# devkit.net
KiCad netlist of a schematic drawn in EAGLE
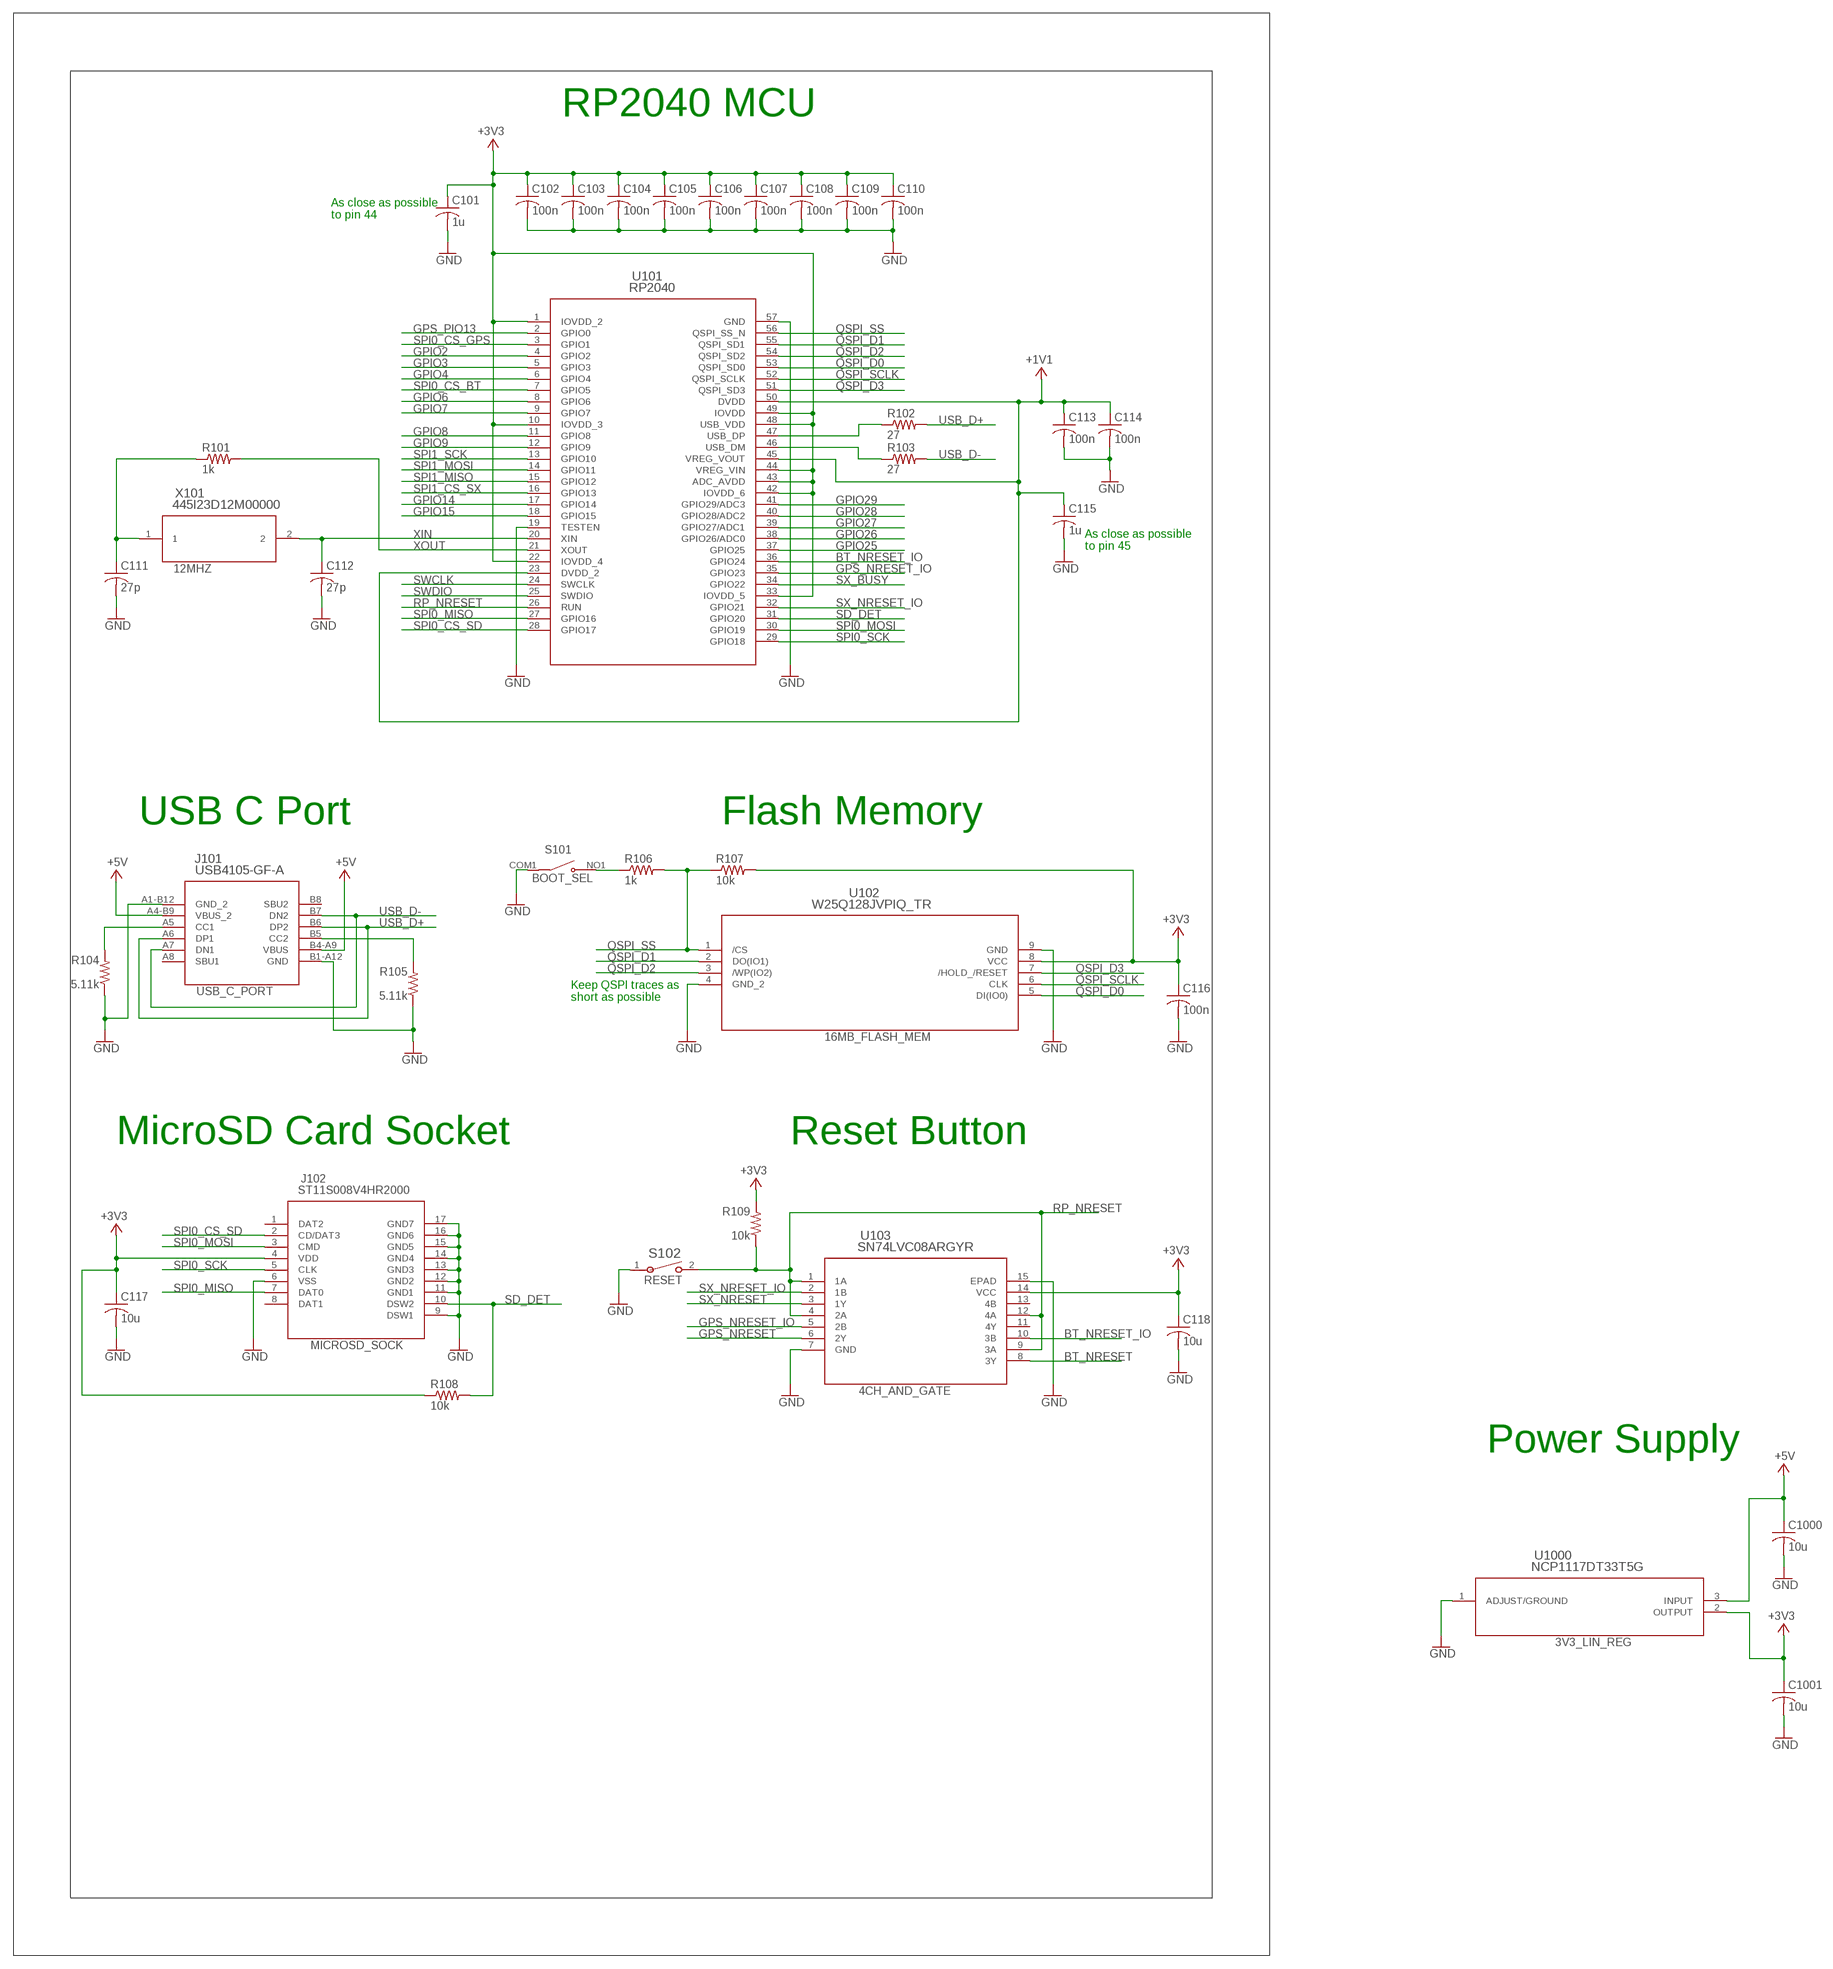
[diagram p0: schematic, sheet 1]
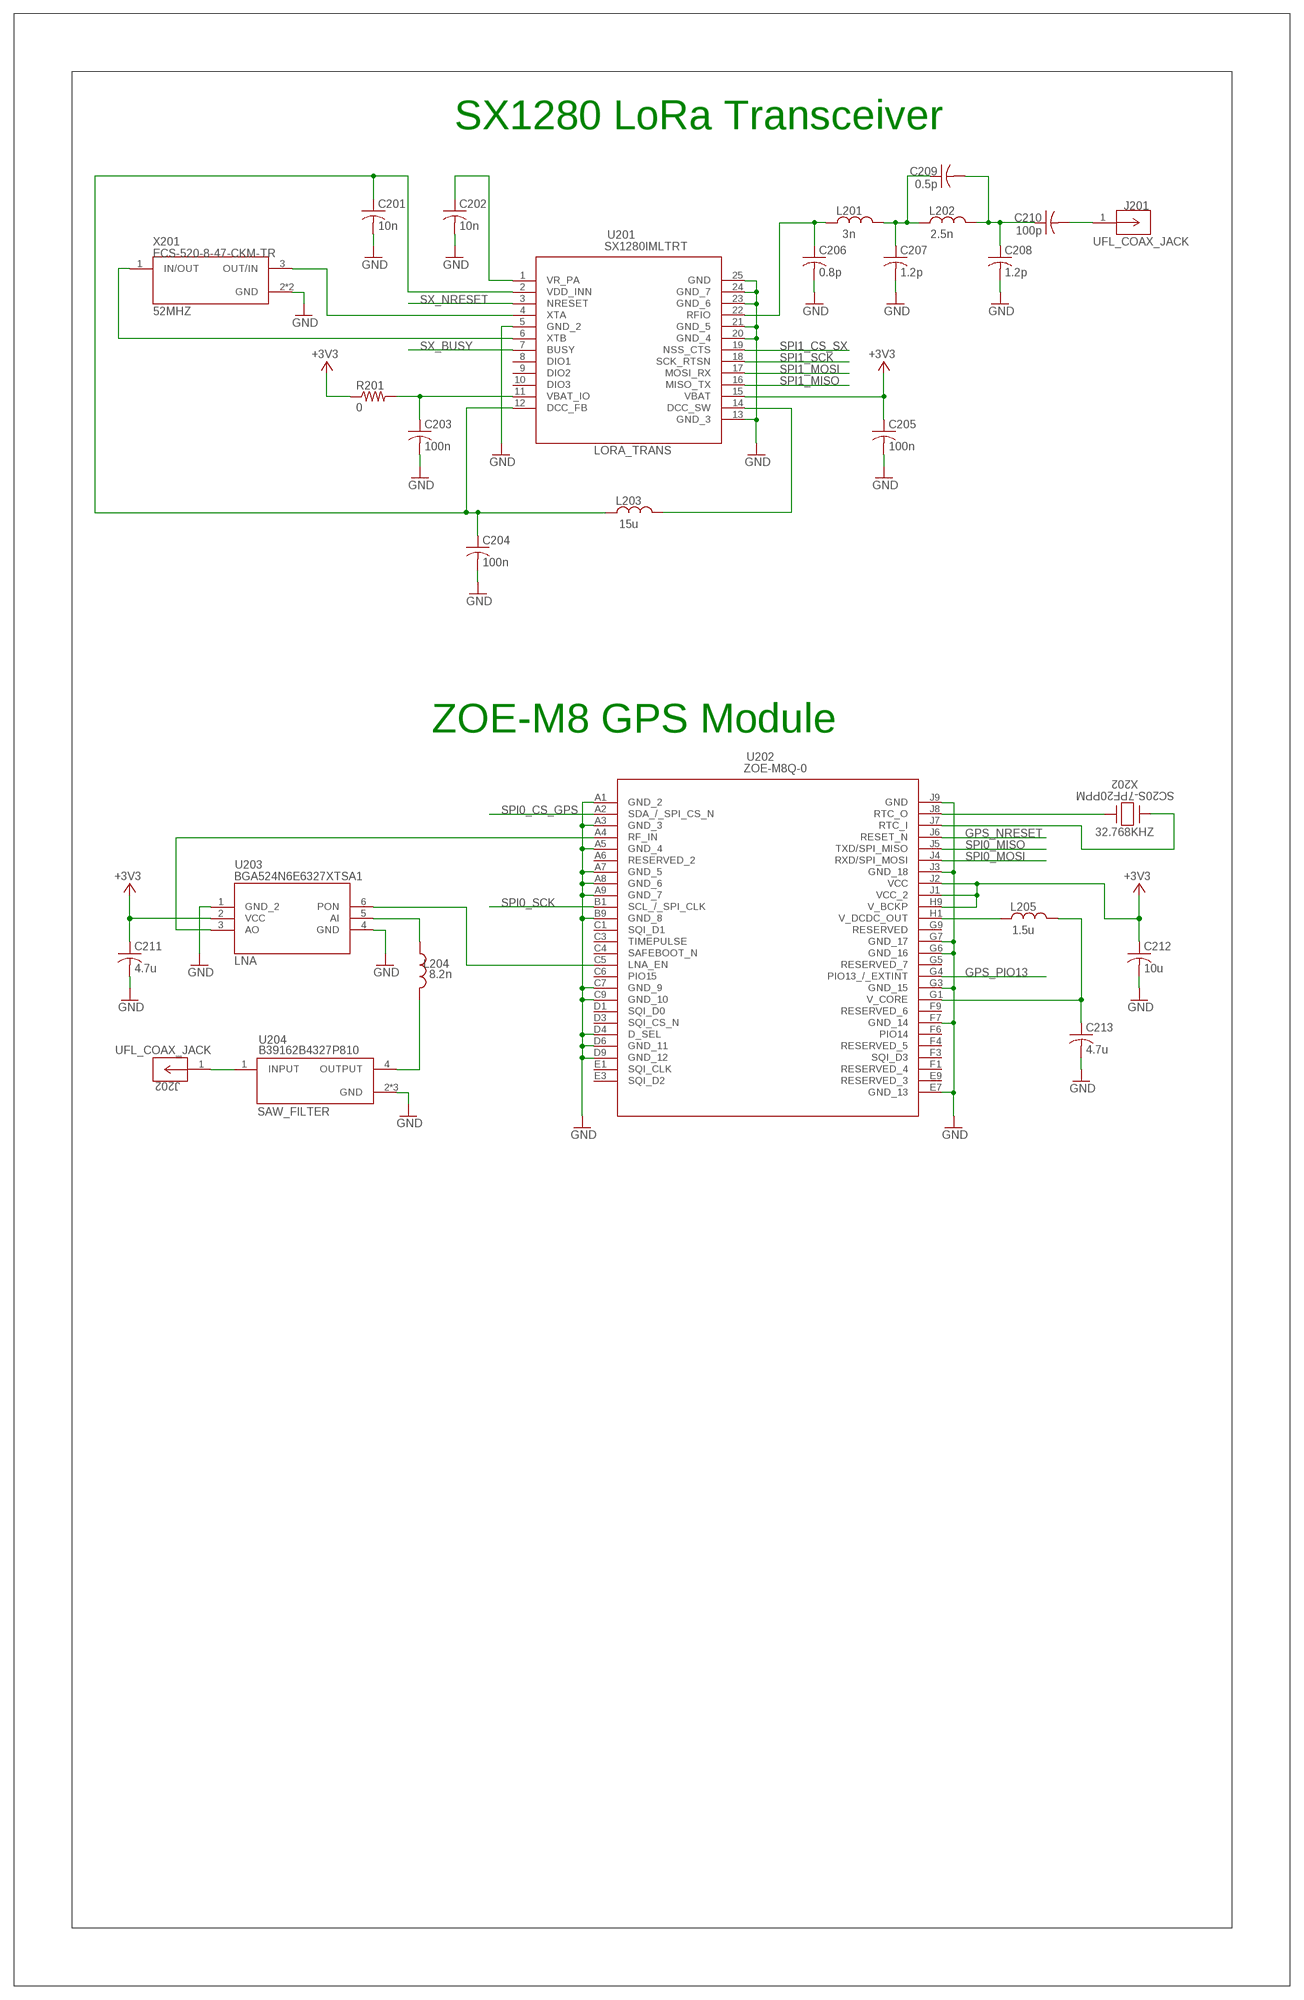
[diagram p1: schematic, sheet 2]

(export (version "E")
  (design (tool "Eeschema 10.0.6"))
  (components
    (comp (ref "C101")
      (value "1u")
      (footprint "eagle-import:C0402")
      (libsource (lib "eagle-import") (part "C-USC0402"))
    )
    (comp (ref "C102")
      (value "100n")
      (footprint "eagle-import:C0402")
      (libsource (lib "eagle-import") (part "C-USC0402"))
    )
    (comp (ref "C103")
      (value "100n")
      (footprint "eagle-import:C0402")
      (libsource (lib "eagle-import") (part "C-USC0402"))
    )
    (comp (ref "C104")
      (value "100n")
      (footprint "eagle-import:C0402")
      (libsource (lib "eagle-import") (part "C-USC0402"))
    )
    (comp (ref "C105")
      (value "100n")
      (footprint "eagle-import:C0402")
      (libsource (lib "eagle-import") (part "C-USC0402"))
    )
    (comp (ref "C106")
      (value "100n")
      (footprint "eagle-import:C0402")
      (libsource (lib "eagle-import") (part "C-USC0402"))
    )
    (comp (ref "C107")
      (value "100n")
      (footprint "eagle-import:C0402")
      (libsource (lib "eagle-import") (part "C-USC0402"))
    )
    (comp (ref "C108")
      (value "100n")
      (footprint "eagle-import:C0402")
      (libsource (lib "eagle-import") (part "C-USC0402"))
    )
    (comp (ref "C109")
      (value "100n")
      (footprint "eagle-import:C0402")
      (libsource (lib "eagle-import") (part "C-USC0402"))
    )
    (comp (ref "C110")
      (value "100n")
      (footprint "eagle-import:C0402")
      (libsource (lib "eagle-import") (part "C-USC0402"))
    )
    (comp (ref "C111")
      (value "27p")
      (footprint "eagle-import:C0402")
      (libsource (lib "eagle-import") (part "C-USC0402"))
    )
    (comp (ref "C112")
      (value "27p")
      (footprint "eagle-import:C0402")
      (libsource (lib "eagle-import") (part "C-USC0402"))
    )
    (comp (ref "C113")
      (value "100n")
      (footprint "eagle-import:C0402")
      (libsource (lib "eagle-import") (part "C-USC0402"))
    )
    (comp (ref "C114")
      (value "100n")
      (footprint "eagle-import:C0402")
      (libsource (lib "eagle-import") (part "C-USC0402"))
    )
    (comp (ref "C115")
      (value "1u")
      (footprint "eagle-import:C0402")
      (libsource (lib "eagle-import") (part "C-USC0402"))
    )
    (comp (ref "C116")
      (value "100n")
      (footprint "eagle-import:C0402")
      (libsource (lib "eagle-import") (part "C-USC0402"))
    )
    (comp (ref "C117")
      (value "10u")
      (footprint "eagle-import:C0402")
      (libsource (lib "eagle-import") (part "C-USC0402"))
    )
    (comp (ref "C118")
      (value "10u")
      (footprint "eagle-import:C0402")
      (libsource (lib "eagle-import") (part "C-USC0402"))
    )
    (comp (ref "C1000")
      (value "10u")
      (footprint "eagle-import:C0402")
      (libsource (lib "eagle-import") (part "C-USC0402"))
    )
    (comp (ref "C1001")
      (value "10u")
      (footprint "eagle-import:C0402")
      (libsource (lib "eagle-import") (part "C-USC0402"))
    )
    (comp (ref "J101")
      (value "USB4105-GF-A")
      (footprint "eagle-import:USB4105_GCT")
      (description "USB_C_PORT")
      (fields (field (name "COPYRIGHT") "Copyright (C) 2022 Ultra Librarian. All rights reserved."))
      (libsource (lib "eagle-import") (part "USB4105-GF-A"))
    )
    (comp (ref "J102")
      (value "ST11S008V4HR2000")
      (footprint "eagle-import:ST11S008V4HR2000_JAE")
      (description "MICROSD_SOCK")
      (fields (field (name "COPYRIGHT") "Copyright (C) 2022 Ultra Librarian. All rights reserved."))
      (libsource (lib "eagle-import") (part "ST11S008V4HR2000"))
    )
    (comp (ref "R101")
      (value "1k")
      (footprint "eagle-import:R0402")
      (libsource (lib "eagle-import") (part "R-US_R0402"))
    )
    (comp (ref "R102")
      (value "27")
      (footprint "eagle-import:R0402")
      (libsource (lib "eagle-import") (part "R-US_R0402"))
    )
    (comp (ref "R103")
      (value "27")
      (footprint "eagle-import:R0402")
      (libsource (lib "eagle-import") (part "R-US_R0402"))
    )
    (comp (ref "R104")
      (value "5.11k")
      (footprint "eagle-import:R0402")
      (libsource (lib "eagle-import") (part "R-US_R0402"))
    )
    (comp (ref "R105")
      (value "5.11k")
      (footprint "eagle-import:R0402")
      (libsource (lib "eagle-import") (part "R-US_R0402"))
    )
    (comp (ref "R106")
      (value "1k")
      (footprint "eagle-import:R0402")
      (libsource (lib "eagle-import") (part "R-US_R0402"))
    )
    (comp (ref "R107")
      (value "10k")
      (footprint "eagle-import:R0402")
      (libsource (lib "eagle-import") (part "R-US_R0402"))
    )
    (comp (ref "R108")
      (value "10k")
      (footprint "eagle-import:R0402")
      (libsource (lib "eagle-import") (part "R-US_R0402"))
    )
    (comp (ref "R109")
      (value "10k")
      (footprint "eagle-import:R0402")
      (libsource (lib "eagle-import") (part "R-US_R0402"))
    )
    (comp (ref "S101")
      (value "SDA01H1SBD")
      (footprint "eagle-import:SW_SDA01H1SBD")
      (description "BOOT_SEL")
      (fields (field (name "DIGI-KEY_PART_NUMBER") "CKN10358-ND") (field (name "MF") "C&K"))
      (libsource (lib "eagle-import") (part "SDA01H1SBD"))
    )
    (comp (ref "S102")
      (value "PTS820J25MSMTRLFS")
      (footprint "eagle-import:SW2_PTS820J25MSMTRLFS_CNK")
      (description "RESET")
      (fields (field (name "COPYRIGHT") "Copyright (C) 2022 Ultra Librarian. All rights reserved."))
      (libsource (lib "eagle-import") (part "PTS820J25MSMTRLFS"))
    )
    (comp (ref "U101")
      (value "RP2040")
      (footprint "eagle-import:IC57_RP2040")
      (fields
        (field (name "MANUFACTURER_PART_NUMBER") "SC0908(13)")
        (field (name "COPYRIGHT") "Copyright (C) 2022 Ultra Librarian. All rights reserved.")
      )
      (libsource (lib "eagle-import") (part "SC0908(13)"))
    )
    (comp (ref "U102")
      (value "W25Q128JVPIQ_TR")
      (footprint "eagle-import:WSON-8_6X5_WIN")
      (description "16MB_FLASH_MEM")
      (fields
        (field (name "MANUFACTURER_PART_NUMBER") "W25Q128JVPIQ TR")
        (field (name "COPYRIGHT") "Copyright (C) 2022 Ultra Librarian. All rights reserved.")
      )
      (libsource (lib "eagle-import") (part "W25Q128JVPIQ_TR"))
    )
    (comp (ref "U103")
      (value "SN74LVC08ARGYR")
      (footprint "eagle-import:RGY14_2P05X2P05")
      (description "4CH_AND_GATE")
      (fields (field (name "COPYRIGHT") "Copyright (C) 2022 Ultra Librarian. All rights reserved."))
      (libsource (lib "eagle-import") (part "SN74LVC08ARGYR"))
    )
    (comp (ref "U1000")
      (value "NCP1117DT33T5G")
      (footprint "eagle-import:DPAK-3_ONS")
      (description "3V3_LIN_REG")
      (fields (field (name "COPYRIGHT") "Copyright (C) 2022 Ultra Librarian. All rights reserved."))
      (libsource (lib "eagle-import") (part "NCP1117DT33T5G"))
    )
    (comp (ref "X101")
      (value "445I23D12M00000")
      (footprint "eagle-import:445I23D12M00000_CTS")
      (description "12MHZ")
      (fields (field (name "COPYRIGHT") "Copyright (C) 2022 Ultra Librarian. All rights reserved."))
      (libsource (lib "eagle-import") (part "445I23D12M00000"))
    )
    (comp (ref "C201")
      (value "10n")
      (footprint "eagle-import:C0402")
      (libsource (lib "eagle-import") (part "C-USC0402"))
    )
    (comp (ref "C202")
      (value "10n")
      (footprint "eagle-import:C0402")
      (libsource (lib "eagle-import") (part "C-USC0402"))
    )
    (comp (ref "C203")
      (value "100n")
      (footprint "eagle-import:C0402")
      (libsource (lib "eagle-import") (part "C-USC0402"))
    )
    (comp (ref "C204")
      (value "100n")
      (footprint "eagle-import:C0402")
      (libsource (lib "eagle-import") (part "C-USC0402"))
    )
    (comp (ref "C205")
      (value "100n")
      (footprint "eagle-import:C0402")
      (libsource (lib "eagle-import") (part "C-USC0402"))
    )
    (comp (ref "C206")
      (value "0.8p")
      (footprint "eagle-import:C0402")
      (libsource (lib "eagle-import") (part "C-USC0402"))
    )
    (comp (ref "C207")
      (value "1.2p")
      (footprint "eagle-import:C0402")
      (libsource (lib "eagle-import") (part "C-USC0402"))
    )
    (comp (ref "C208")
      (value "1.2p")
      (footprint "eagle-import:C0402")
      (libsource (lib "eagle-import") (part "C-USC0402"))
    )
    (comp (ref "C209")
      (value "0.5p")
      (footprint "eagle-import:C0402")
      (libsource (lib "eagle-import") (part "C-USC0402"))
    )
    (comp (ref "C210")
      (value "100p")
      (footprint "eagle-import:C0402")
      (libsource (lib "eagle-import") (part "C-USC0402"))
    )
    (comp (ref "C211")
      (value "4.7u")
      (footprint "eagle-import:C0402")
      (libsource (lib "eagle-import") (part "C-USC0402"))
    )
    (comp (ref "C212")
      (value "10u")
      (footprint "eagle-import:C0402")
      (libsource (lib "eagle-import") (part "C-USC0402"))
    )
    (comp (ref "C213")
      (value "4.7u")
      (footprint "eagle-import:C0402")
      (libsource (lib "eagle-import") (part "C-USC0402"))
    )
    (comp (ref "J201")
      (value "CONUFL001-SMD-T")
      (footprint "eagle-import:CONN_CONUFL001-SMD-T_LNX")
      (description "UFL_COAX_JACK")
      (fields (field (name "COPYRIGHT") "Copyright (C) 2022 Ultra Librarian. All rights reserved."))
      (libsource (lib "eagle-import") (part "CONUFL001-SMD-T"))
    )
    (comp (ref "J202")
      (value "CONUFL001-SMD-T")
      (footprint "eagle-import:CONN_CONUFL001-SMD-T_LNX")
      (description "UFL_COAX_JACK")
      (fields (field (name "COPYRIGHT") "Copyright (C) 2022 Ultra Librarian. All rights reserved."))
      (libsource (lib "eagle-import") (part "CONUFL001-SMD-T"))
    )
    (comp (ref "L201")
      (value "3n")
      (footprint "eagle-import:INDC1006X60N")
      (libsource (lib "eagle-import") (part "LCHIP-0402(1006-METRIC)_"))
    )
    (comp (ref "L202")
      (value "2.5n")
      (footprint "eagle-import:INDC1006X60N")
      (libsource (lib "eagle-import") (part "LCHIP-0402(1006-METRIC)_"))
    )
    (comp (ref "L203")
      (value "15u")
      (footprint "eagle-import:INDC2009X120")
      (libsource (lib "eagle-import") (part "LCHIP-0805(2012-METRIC)_"))
    )
    (comp (ref "L204")
      (value "8.2n")
      (footprint "eagle-import:INDC1006X60N")
      (libsource (lib "eagle-import") (part "LCHIP-0402(1006-METRIC)_"))
    )
    (comp (ref "L205")
      (value "1.5u")
      (footprint "eagle-import:INDC2009X120")
      (libsource (lib "eagle-import") (part "LCHIP-0805(2012-METRIC)_"))
    )
    (comp (ref "R201")
      (value "0")
      (footprint "eagle-import:R0402")
      (libsource (lib "eagle-import") (part "R-US_R0402"))
    )
    (comp (ref "U201")
      (value "SX1280IMLTRT")
      (footprint "eagle-import:QFN24_4X4_SEM")
      (description "LORA_TRANS")
      (fields (field (name "COPYRIGHT") "Copyright (C) 2022 Ultra Librarian. All rights reserved."))
      (libsource (lib "eagle-import") (part "SX1280IMLTRT"))
    )
    (comp (ref "U202")
      (value "ZOE-M8Q-0")
      (footprint "eagle-import:BGA_E-M8Q-0_UBL")
      (fields (field (name "COPYRIGHT") "Copyright (C) 2022 Ultra Librarian. All rights reserved."))
      (libsource (lib "eagle-import") (part "ZOE-M8Q-0"))
    )
    (comp (ref "U203")
      (value "BGA524N6E6327XTSA1")
      (footprint "eagle-import:PG-TSNP-6-2_INF")
      (description "LNA")
      (fields (field (name "COPYRIGHT") "Copyright (C) 2022 Ultra Librarian. All rights reserved."))
      (libsource (lib "eagle-import") (part "BGA524N6E6327XTSA1"))
    )
    (comp (ref "U204")
      (value "B39162B4327P810")
      (footprint "eagle-import:FIL_B39162B4327P810")
      (fields
        (field (name "DIGI-KEY_PART_NUMBER") "495-7424-2-ND")
        (field (name "MF") "Qualcomm (RF360")
        (field (name "DECRIPTION") "SAW_FILTER")
      )
      (libsource (lib "eagle-import") (part "B39162B4327P810"))
    )
    (comp (ref "X201")
      (value "ECS-520-8-47-CKM-TR")
      (footprint "eagle-import:XTAL_ECS-520-8-47-CKM-TR")
      (description "52MHZ")
      (fields (field (name "DIGI-KEY_PART_NUMBER") "XC2554TR-ND") (field (name "MF") "ECS Inc."))
      (libsource (lib "eagle-import") (part "ECS-520-8-47-CKM-TR"))
    )
    (comp (ref "X202")
      (value "SC20S-7PF20PPM")
      (footprint "eagle-import:XTAL_SC-20S_EPS")
      (description "32.768KHZ")
      (fields (field (name "COPYRIGHT") "Copyright (C) 2022 Ultra Librarian. All rights reserved."))
      (libsource (lib "eagle-import") (part "SC20S-7PF20PPM"))
    )
  )
  (nets
    (net (code "1") (name "+1V1") (class "Default")
      (node (ref "C113") (pin "1") (pinfunction "1_1") (pintype "passive"))
      (node (ref "C114") (pin "1") (pinfunction "1_1") (pintype "passive"))
      (node (ref "C115") (pin "1") (pinfunction "1_1") (pintype "passive"))
      (node (ref "U101") (pin "23") (pinfunction "DVDD_2_23") (pintype "power_in"))
      (node (ref "U101") (pin "45") (pinfunction "VREG_VOUT_45") (pintype "output"))
      (node (ref "U101") (pin "50") (pinfunction "DVDD_50") (pintype "power_in"))
    )
    (net (code "2") (name "+3V3") (class "Default")
      (node (ref "C1001") (pin "1") (pinfunction "1_1") (pintype "passive"))
      (node (ref "C101") (pin "1") (pinfunction "1_1") (pintype "passive"))
      (node (ref "C102") (pin "1") (pinfunction "1_1") (pintype "passive"))
      (node (ref "C103") (pin "1") (pinfunction "1_1") (pintype "passive"))
      (node (ref "C104") (pin "1") (pinfunction "1_1") (pintype "passive"))
      (node (ref "C105") (pin "1") (pinfunction "1_1") (pintype "passive"))
      (node (ref "C106") (pin "1") (pinfunction "1_1") (pintype "passive"))
      (node (ref "C107") (pin "1") (pinfunction "1_1") (pintype "passive"))
      (node (ref "C108") (pin "1") (pinfunction "1_1") (pintype "passive"))
      (node (ref "C109") (pin "1") (pinfunction "1_1") (pintype "passive"))
      (node (ref "C110") (pin "1") (pinfunction "1_1") (pintype "passive"))
      (node (ref "C116") (pin "1") (pinfunction "1_1") (pintype "passive"))
      (node (ref "C117") (pin "1") (pinfunction "1_1") (pintype "passive"))
      (node (ref "C118") (pin "1") (pinfunction "1_1") (pintype "passive"))
      (node (ref "C205") (pin "1") (pinfunction "1_1") (pintype "passive"))
      (node (ref "C211") (pin "1") (pinfunction "1_1") (pintype "passive"))
      (node (ref "C212") (pin "1") (pinfunction "1_1") (pintype "passive"))
      (node (ref "J102") (pin "4") (pinfunction "VDD_4") (pintype "power_in"))
      (node (ref "R107") (pin "2") (pinfunction "2_2") (pintype "passive"))
      (node (ref "R108") (pin "1") (pinfunction "1_1") (pintype "passive"))
      (node (ref "R109") (pin "2") (pinfunction "2_2") (pintype "passive"))
      (node (ref "R201") (pin "1") (pinfunction "1_1") (pintype "passive"))
      (node (ref "U1000") (pin "2") (pinfunction "OUTPUT_2") (pintype "output"))
      (node (ref "U101") (pin "1") (pinfunction "IOVDD_2_1") (pintype "power_in"))
      (node (ref "U101") (pin "10") (pinfunction "IOVDD_3_10") (pintype "power_in"))
      (node (ref "U101") (pin "22") (pinfunction "IOVDD_4_22") (pintype "power_in"))
      (node (ref "U101") (pin "33") (pinfunction "IOVDD_5_33") (pintype "power_in"))
      (node (ref "U101") (pin "42") (pinfunction "IOVDD_6_42") (pintype "power_in"))
      (node (ref "U101") (pin "43") (pinfunction "ADC_AVDD_43") (pintype "power_in"))
      (node (ref "U101") (pin "44") (pinfunction "VREG_VIN_44") (pintype "passive"))
      (node (ref "U101") (pin "48") (pinfunction "USB_VDD_48") (pintype "power_in"))
      (node (ref "U101") (pin "49") (pinfunction "IOVDD_49") (pintype "power_in"))
      (node (ref "U102") (pin "8") (pinfunction "VCC_8") (pintype "power_in"))
      (node (ref "U103") (pin "14") (pinfunction "VCC_14") (pintype "power_in"))
      (node (ref "U201") (pin "15") (pinfunction "VBAT_15") (pintype "power_in"))
      (node (ref "U202") (pin "H9") (pinfunction "V_BCKP_H9") (pintype "passive"))
      (node (ref "U202") (pin "J1") (pinfunction "VCC_2_J1") (pintype "power_in"))
      (node (ref "U202") (pin "J2") (pinfunction "VCC_J2") (pintype "power_in"))
      (node (ref "U203") (pin "2") (pinfunction "VCC_2") (pintype "power_in"))
    )
    (net (code "3") (name "+5V") (class "Default")
      (node (ref "C1000") (pin "1") (pinfunction "1_1") (pintype "passive"))
      (node (ref "J101") (pin "A4-B9") (pinfunction "VBUS_2_A4-B9") (pintype "power_in"))
      (node (ref "J101") (pin "B4-A9") (pinfunction "VBUS_B4-A9") (pintype "power_in"))
      (node (ref "U1000") (pin "3") (pinfunction "INPUT_3") (pintype "input"))
    )
    (net (code "4") (name "BT_NRESET") (class "Default")
      (node (ref "U103") (pin "8") (pinfunction "3Y_8") (pintype "output"))
    )
    (net (code "5") (name "BT_NRESET_IO") (class "Default")
      (node (ref "U101") (pin "36") (pinfunction "GPIO24_36") (pintype "bidirectional"))
      (node (ref "U103") (pin "10") (pinfunction "3B_10") (pintype "input"))
    )
    (net (code "6") (name "GND") (class "Default")
      (node (ref "C1000") (pin "2") (pinfunction "2_2") (pintype "passive"))
      (node (ref "C1001") (pin "2") (pinfunction "2_2") (pintype "passive"))
      (node (ref "C101") (pin "2") (pinfunction "2_2") (pintype "passive"))
      (node (ref "C102") (pin "2") (pinfunction "2_2") (pintype "passive"))
      (node (ref "C103") (pin "2") (pinfunction "2_2") (pintype "passive"))
      (node (ref "C104") (pin "2") (pinfunction "2_2") (pintype "passive"))
      (node (ref "C105") (pin "2") (pinfunction "2_2") (pintype "passive"))
      (node (ref "C106") (pin "2") (pinfunction "2_2") (pintype "passive"))
      (node (ref "C107") (pin "2") (pinfunction "2_2") (pintype "passive"))
      (node (ref "C108") (pin "2") (pinfunction "2_2") (pintype "passive"))
      (node (ref "C109") (pin "2") (pinfunction "2_2") (pintype "passive"))
      (node (ref "C110") (pin "2") (pinfunction "2_2") (pintype "passive"))
      (node (ref "C111") (pin "2") (pinfunction "2_2") (pintype "passive"))
      (node (ref "C112") (pin "2") (pinfunction "2_2") (pintype "passive"))
      (node (ref "C113") (pin "2") (pinfunction "2_2") (pintype "passive"))
      (node (ref "C114") (pin "2") (pinfunction "2_2") (pintype "passive"))
      (node (ref "C115") (pin "2") (pinfunction "2_2") (pintype "passive"))
      (node (ref "C116") (pin "2") (pinfunction "2_2") (pintype "passive"))
      (node (ref "C117") (pin "2") (pinfunction "2_2") (pintype "passive"))
      (node (ref "C118") (pin "2") (pinfunction "2_2") (pintype "passive"))
      (node (ref "C201") (pin "2") (pinfunction "2_2") (pintype "passive"))
      (node (ref "C202") (pin "2") (pinfunction "2_2") (pintype "passive"))
      (node (ref "C203") (pin "2") (pinfunction "2_2") (pintype "passive"))
      (node (ref "C204") (pin "2") (pinfunction "2_2") (pintype "passive"))
      (node (ref "C205") (pin "2") (pinfunction "2_2") (pintype "passive"))
      (node (ref "C206") (pin "2") (pinfunction "2_2") (pintype "passive"))
      (node (ref "C207") (pin "2") (pinfunction "2_2") (pintype "passive"))
      (node (ref "C208") (pin "2") (pinfunction "2_2") (pintype "passive"))
      (node (ref "C211") (pin "2") (pinfunction "2_2") (pintype "passive"))
      (node (ref "C212") (pin "2") (pinfunction "2_2") (pintype "passive"))
      (node (ref "C213") (pin "2") (pinfunction "2_2") (pintype "passive"))
      (node (ref "J101") (pin "A1-B12") (pinfunction "GND_2_A1-B12") (pintype "passive"))
      (node (ref "J101") (pin "B1-A12") (pinfunction "GND_B1-A12") (pintype "passive"))
      (node (ref "J102") (pin "11") (pinfunction "GND1_11") (pintype "passive"))
      (node (ref "J102") (pin "12") (pinfunction "GND2_12") (pintype "passive"))
      (node (ref "J102") (pin "13") (pinfunction "GND3_13") (pintype "passive"))
      (node (ref "J102") (pin "14") (pinfunction "GND4_14") (pintype "passive"))
      (node (ref "J102") (pin "15") (pinfunction "GND5_15") (pintype "passive"))
      (node (ref "J102") (pin "16") (pinfunction "GND6_16") (pintype "passive"))
      (node (ref "J102") (pin "17") (pinfunction "GND7_17") (pintype "passive"))
      (node (ref "J102") (pin "6") (pinfunction "VSS_6") (pintype "passive"))
      (node (ref "J102") (pin "9") (pinfunction "DSW1_9") (pintype "bidirectional"))
      (node (ref "R104") (pin "1") (pinfunction "1_1") (pintype "passive"))
      (node (ref "R105") (pin "1") (pinfunction "1_1") (pintype "passive"))
      (node (ref "S101") (pin "COM1") (pinfunction "COM_COM1") (pintype "passive"))
      (node (ref "S102") (pin "1") (pinfunction "1_1") (pintype "passive"))
      (node (ref "U1000") (pin "1") (pinfunction "ADJUST/GROUND_1") (pintype "bidirectional"))
      (node (ref "U101") (pin "19") (pinfunction "TESTEN_19") (pintype "passive"))
      (node (ref "U101") (pin "57") (pinfunction "GND_57") (pintype "passive"))
      (node (ref "U102") (pin "4") (pinfunction "GND_2_4") (pintype "passive"))
      (node (ref "U102") (pin "9") (pinfunction "GND_9") (pintype "passive"))
      (node (ref "U103") (pin "15") (pinfunction "EPAD_15") (pintype "passive"))
      (node (ref "U103") (pin "7") (pinfunction "GND_7") (pintype "power_in"))
      (node (ref "U201") (pin "13") (pinfunction "GND_3_13") (pintype "passive"))
      (node (ref "U201") (pin "20") (pinfunction "GND_4_20") (pintype "passive"))
      (node (ref "U201") (pin "21") (pinfunction "GND_5_21") (pintype "passive"))
      (node (ref "U201") (pin "23") (pinfunction "GND_6_23") (pintype "passive"))
      (node (ref "U201") (pin "24") (pinfunction "GND_7_24") (pintype "passive"))
      (node (ref "U201") (pin "25") (pinfunction "GND_25") (pintype "passive"))
      (node (ref "U201") (pin "5") (pinfunction "GND_2_5") (pintype "passive"))
      (node (ref "U202") (pin "A1") (pinfunction "GND_2_A1") (pintype "passive"))
      (node (ref "U202") (pin "A3") (pinfunction "GND_3_A3") (pintype "passive"))
      (node (ref "U202") (pin "A5") (pinfunction "GND_4_A5") (pintype "passive"))
      (node (ref "U202") (pin "A7") (pinfunction "GND_5_A7") (pintype "passive"))
      (node (ref "U202") (pin "A8") (pinfunction "GND_6_A8") (pintype "passive"))
      (node (ref "U202") (pin "A9") (pinfunction "GND_7_A9") (pintype "passive"))
      (node (ref "U202") (pin "B9") (pinfunction "GND_8_B9") (pintype "passive"))
      (node (ref "U202") (pin "C7") (pinfunction "GND_9_C7") (pintype "passive"))
      (node (ref "U202") (pin "C9") (pinfunction "GND_10_C9") (pintype "passive"))
      (node (ref "U202") (pin "D4") (pinfunction "D_SEL_D4") (pintype "passive"))
      (node (ref "U202") (pin "D6") (pinfunction "GND_11_D6") (pintype "passive"))
      (node (ref "U202") (pin "D9") (pinfunction "GND_12_D9") (pintype "passive"))
      (node (ref "U202") (pin "E7") (pinfunction "GND_13_E7") (pintype "passive"))
      (node (ref "U202") (pin "F7") (pinfunction "GND_14_F7") (pintype "passive"))
      (node (ref "U202") (pin "G3") (pinfunction "GND_15_G3") (pintype "passive"))
      (node (ref "U202") (pin "G6") (pinfunction "GND_16_G6") (pintype "passive"))
      (node (ref "U202") (pin "G7") (pinfunction "GND_17_G7") (pintype "passive"))
      (node (ref "U202") (pin "J3") (pinfunction "GND_18_J3") (pintype "passive"))
      (node (ref "U202") (pin "J9") (pinfunction "GND_J9") (pintype "passive"))
      (node (ref "U203") (pin "1") (pinfunction "GND_2_1") (pintype "passive"))
      (node (ref "U203") (pin "4") (pinfunction "GND_4") (pintype "passive"))
      (node (ref "U204") (pin "2") (pinfunction "GND_2") (pintype "power_in"))
      (node (ref "U204") (pin "3") (pinfunction "GND_3") (pintype "power_in"))
      (node (ref "U204") (pin "5") (pinfunction "GND_5") (pintype "power_in"))
      (node (ref "X201") (pin "2") (pinfunction "GND_2") (pintype "power_in"))
      (node (ref "X201") (pin "4") (pinfunction "GND_4") (pintype "power_in"))
    )
    (net (code "7") (name "GPIO2") (class "Default")
      (node (ref "U101") (pin "4") (pinfunction "GPIO2_4") (pintype "bidirectional"))
    )
    (net (code "8") (name "GPIO3") (class "Default")
      (node (ref "U101") (pin "5") (pinfunction "GPIO3_5") (pintype "bidirectional"))
    )
    (net (code "9") (name "GPIO4") (class "Default")
      (node (ref "U101") (pin "6") (pinfunction "GPIO4_6") (pintype "bidirectional"))
    )
    (net (code "10") (name "GPIO6") (class "Default")
      (node (ref "U101") (pin "8") (pinfunction "GPIO6_8") (pintype "bidirectional"))
    )
    (net (code "11") (name "GPIO7") (class "Default")
      (node (ref "U101") (pin "9") (pinfunction "GPIO7_9") (pintype "bidirectional"))
    )
    (net (code "12") (name "GPIO8") (class "Default")
      (node (ref "U101") (pin "11") (pinfunction "GPIO8_11") (pintype "bidirectional"))
    )
    (net (code "13") (name "GPIO9") (class "Default")
      (node (ref "U101") (pin "12") (pinfunction "GPIO9_12") (pintype "bidirectional"))
    )
    (net (code "14") (name "GPIO14") (class "Default")
      (node (ref "U101") (pin "17") (pinfunction "GPIO14_17") (pintype "bidirectional"))
    )
    (net (code "15") (name "GPIO15") (class "Default")
      (node (ref "U101") (pin "18") (pinfunction "GPIO15_18") (pintype "bidirectional"))
    )
    (net (code "16") (name "GPIO25") (class "Default")
      (node (ref "U101") (pin "37") (pinfunction "GPIO25_37") (pintype "bidirectional"))
    )
    (net (code "17") (name "GPIO26") (class "Default")
      (node (ref "U101") (pin "38") (pinfunction "GPIO26/ADC0_38") (pintype "bidirectional"))
    )
    (net (code "18") (name "GPIO27") (class "Default")
      (node (ref "U101") (pin "39") (pinfunction "GPIO27/ADC1_39") (pintype "bidirectional"))
    )
    (net (code "19") (name "GPIO28") (class "Default")
      (node (ref "U101") (pin "40") (pinfunction "GPIO28/ADC2_40") (pintype "bidirectional"))
    )
    (net (code "20") (name "GPIO29") (class "Default")
      (node (ref "U101") (pin "41") (pinfunction "GPIO29/ADC3_41") (pintype "bidirectional"))
    )
    (net (code "21") (name "GPS_NRESET") (class "Default")
      (node (ref "U103") (pin "6") (pinfunction "2Y_6") (pintype "output"))
      (node (ref "U202") (pin "J6") (pinfunction "RESET_N_J6") (pintype "passive"))
    )
    (net (code "22") (name "GPS_NRESET_IO") (class "Default")
      (node (ref "U101") (pin "35") (pinfunction "GPIO23_35") (pintype "bidirectional"))
      (node (ref "U103") (pin "5") (pinfunction "2B_5") (pintype "input"))
    )
    (net (code "23") (name "GPS_PIO13") (class "Default")
      (node (ref "U101") (pin "2") (pinfunction "GPIO0_2") (pintype "bidirectional"))
      (node (ref "U202") (pin "G4") (pinfunction "PIO13_/_EXTINT_G4") (pintype "bidirectional"))
    )
    (net (code "24") (name "Net-(C111-Pad1)") (class "Default")
      (node (ref "C111") (pin "1") (pinfunction "1_1") (pintype "passive"))
      (node (ref "R101") (pin "1") (pinfunction "1_1") (pintype "passive"))
      (node (ref "X101") (pin "1") (pinfunction "1_1") (pintype "passive"))
    )
    (net (code "25") (name "Net-(C207-Pad1)") (class "Default")
      (node (ref "C207") (pin "1") (pinfunction "1_1") (pintype "passive"))
      (node (ref "C209") (pin "1") (pinfunction "1_1") (pintype "passive"))
      (node (ref "L201") (pin "2") (pinfunction "2_2") (pintype "passive"))
      (node (ref "L202") (pin "1") (pinfunction "1_1") (pintype "passive"))
    )
    (net (code "26") (name "Net-(C208-Pad1)") (class "Default")
      (node (ref "C208") (pin "1") (pinfunction "1_1") (pintype "passive"))
      (node (ref "C209") (pin "2") (pinfunction "2_2") (pintype "passive"))
      (node (ref "C210") (pin "1") (pinfunction "1_1") (pintype "passive"))
      (node (ref "L202") (pin "2") (pinfunction "2_2") (pintype "passive"))
    )
    (net (code "27") (name "Net-(C210-Pad2)") (class "Default")
      (node (ref "C210") (pin "2") (pinfunction "2_2") (pintype "passive"))
      (node (ref "J201") (pin "1") (pinfunction "1_1") (pintype "passive"))
    )
    (net (code "28") (name "Net-(J101-CC1)") (class "Default")
      (node (ref "J101") (pin "A5") (pinfunction "CC1_A5") (pintype "bidirectional"))
      (node (ref "R104") (pin "2") (pinfunction "2_2") (pintype "passive"))
    )
    (net (code "29") (name "Net-(J101-CC2)") (class "Default")
      (node (ref "J101") (pin "B5") (pinfunction "CC2_B5") (pintype "bidirectional"))
      (node (ref "R105") (pin "2") (pinfunction "2_2") (pintype "passive"))
    )
    (net (code "30") (name "Net-(S101-NO)") (class "Default")
      (node (ref "R106") (pin "1") (pinfunction "1_1") (pintype "passive"))
      (node (ref "S101") (pin "NO1") (pinfunction "NO_NO1") (pintype "passive"))
    )
    (net (code "31") (name "Net-(U101-USB_DM)") (class "Default")
      (node (ref "R103") (pin "1") (pinfunction "1_1") (pintype "passive"))
      (node (ref "U101") (pin "46") (pinfunction "USB_DM_46") (pintype "passive"))
    )
    (net (code "32") (name "Net-(U101-USB_DP)") (class "Default")
      (node (ref "R102") (pin "1") (pinfunction "1_1") (pintype "passive"))
      (node (ref "U101") (pin "47") (pinfunction "USB_DP_47") (pintype "passive"))
    )
    (net (code "33") (name "Net-(U201-DCC_FB)") (class "Default")
      (node (ref "C201") (pin "1") (pinfunction "1_1") (pintype "passive"))
      (node (ref "C204") (pin "1") (pinfunction "1_1") (pintype "passive"))
      (node (ref "L203") (pin "1") (pinfunction "1_1") (pintype "passive"))
      (node (ref "U201") (pin "12") (pinfunction "DCC_FB_12") (pintype "output"))
      (node (ref "U201") (pin "2") (pinfunction "VDD_INN_2") (pintype "power_in"))
    )
    (net (code "34") (name "Net-(U201-DCC_SW)") (class "Default")
      (node (ref "L203") (pin "2") (pinfunction "2_2") (pintype "passive"))
      (node (ref "U201") (pin "14") (pinfunction "DCC_SW_14") (pintype "output"))
    )
    (net (code "35") (name "Net-(U201-RFIO)") (class "Default")
      (node (ref "C206") (pin "1") (pinfunction "1_1") (pintype "passive"))
      (node (ref "L201") (pin "1") (pinfunction "1_1") (pintype "passive"))
      (node (ref "U201") (pin "22") (pinfunction "RFIO_22") (pintype "bidirectional"))
    )
    (net (code "36") (name "Net-(U201-VBAT_IO)") (class "Default")
      (node (ref "C203") (pin "1") (pinfunction "1_1") (pintype "passive"))
      (node (ref "R201") (pin "2") (pinfunction "2_2") (pintype "passive"))
      (node (ref "U201") (pin "11") (pinfunction "VBAT_IO_11") (pintype "power_in"))
    )
    (net (code "37") (name "Net-(U201-VR_PA)") (class "Default")
      (node (ref "C202") (pin "1") (pinfunction "1_1") (pintype "passive"))
      (node (ref "U201") (pin "1") (pinfunction "VR_PA_1") (pintype "power_in"))
    )
    (net (code "38") (name "Net-(U201-XTA)") (class "Default")
      (node (ref "U201") (pin "4") (pinfunction "XTA_4") (pintype "bidirectional"))
      (node (ref "X201") (pin "3") (pinfunction "OUT/IN_3") (pintype "bidirectional"))
    )
    (net (code "39") (name "Net-(U201-XTB)") (class "Default")
      (node (ref "U201") (pin "6") (pinfunction "XTB_6") (pintype "bidirectional"))
      (node (ref "X201") (pin "1") (pinfunction "IN/OUT_1") (pintype "bidirectional"))
    )
    (net (code "40") (name "Net-(U202-LNA_EN)") (class "Default")
      (node (ref "U202") (pin "C5") (pinfunction "LNA_EN_C5") (pintype "passive"))
      (node (ref "U203") (pin "6") (pinfunction "PON_6") (pintype "input"))
    )
    (net (code "41") (name "Net-(U202-RF_IN)") (class "Default")
      (node (ref "U202") (pin "A4") (pinfunction "RF_IN_A4") (pintype "passive"))
      (node (ref "U203") (pin "3") (pinfunction "AO_3") (pintype "output"))
    )
    (net (code "42") (name "Net-(U202-RTC_I)") (class "Default")
      (node (ref "U202") (pin "J7") (pinfunction "RTC_I_J7") (pintype "passive"))
      (node (ref "X202") (pin "1") (pinfunction "1_1") (pintype "passive"))
    )
    (net (code "43") (name "Net-(U202-RTC_O)") (class "Default")
      (node (ref "U202") (pin "J8") (pinfunction "RTC_O_J8") (pintype "passive"))
      (node (ref "X202") (pin "2") (pinfunction "2_2") (pintype "passive"))
    )
    (net (code "44") (name "Net-(U202-V_CORE)") (class "Default")
      (node (ref "C213") (pin "1") (pinfunction "1_1") (pintype "passive"))
      (node (ref "L205") (pin "2") (pinfunction "2_2") (pintype "passive"))
      (node (ref "U202") (pin "G1") (pinfunction "V_CORE_G1") (pintype "passive"))
    )
    (net (code "45") (name "Net-(U202-V_DCDC_OUT)") (class "Default")
      (node (ref "L205") (pin "1") (pinfunction "1_1") (pintype "passive"))
      (node (ref "U202") (pin "H1") (pinfunction "V_DCDC_OUT_H1") (pintype "output"))
    )
    (net (code "46") (name "Net-(U203-AI)") (class "Default")
      (node (ref "L204") (pin "1") (pinfunction "1_1") (pintype "passive"))
      (node (ref "U203") (pin "5") (pinfunction "AI_5") (pintype "input"))
    )
    (net (code "47") (name "Net-(U204-INPUT)") (class "Default")
      (node (ref "J202") (pin "1") (pinfunction "1_1") (pintype "passive"))
      (node (ref "U204") (pin "1") (pinfunction "INPUT_1") (pintype "input"))
    )
    (net (code "48") (name "Net-(U204-OUTPUT)") (class "Default")
      (node (ref "L204") (pin "2") (pinfunction "2_2") (pintype "passive"))
      (node (ref "U204") (pin "4") (pinfunction "OUTPUT_4") (pintype "output"))
    )
    (net (code "49") (name "QSPI_D0") (class "Default")
      (node (ref "U101") (pin "53") (pinfunction "QSPI_SD0_53") (pintype "bidirectional"))
      (node (ref "U102") (pin "5") (pinfunction "DI(IO0)_5") (pintype "bidirectional"))
    )
    (net (code "50") (name "QSPI_D1") (class "Default")
      (node (ref "U101") (pin "55") (pinfunction "QSPI_SD1_55") (pintype "bidirectional"))
      (node (ref "U102") (pin "2") (pinfunction "DO(IO1)_2") (pintype "bidirectional"))
    )
    (net (code "51") (name "QSPI_D2") (class "Default")
      (node (ref "U101") (pin "54") (pinfunction "QSPI_SD2_54") (pintype "bidirectional"))
      (node (ref "U102") (pin "3") (pinfunction "/WP(IO2)_3") (pintype "bidirectional"))
    )
    (net (code "52") (name "QSPI_D3") (class "Default")
      (node (ref "U101") (pin "51") (pinfunction "QSPI_SD3_51") (pintype "bidirectional"))
      (node (ref "U102") (pin "7") (pinfunction "/HOLD_/RESET_7") (pintype "bidirectional"))
    )
    (net (code "53") (name "QSPI_SCLK") (class "Default")
      (node (ref "U101") (pin "52") (pinfunction "QSPI_SCLK_52") (pintype "passive"))
      (node (ref "U102") (pin "6") (pinfunction "CLK_6") (pintype "input"))
    )
    (net (code "54") (name "QSPI_SS") (class "Default")
      (node (ref "R106") (pin "2") (pinfunction "2_2") (pintype "passive"))
      (node (ref "R107") (pin "1") (pinfunction "1_1") (pintype "passive"))
      (node (ref "U101") (pin "56") (pinfunction "QSPI_SS_N_56") (pintype "passive"))
      (node (ref "U102") (pin "1") (pinfunction "/CS_1") (pintype "input"))
    )
    (net (code "55") (name "RP_NRESET") (class "Default")
      (node (ref "R109") (pin "1") (pinfunction "1_1") (pintype "passive"))
      (node (ref "S102") (pin "2") (pinfunction "2_2") (pintype "passive"))
      (node (ref "U101") (pin "26") (pinfunction "RUN_26") (pintype "passive"))
      (node (ref "U103") (pin "1") (pinfunction "1A_1") (pintype "input"))
      (node (ref "U103") (pin "12") (pinfunction "4A_12") (pintype "input"))
      (node (ref "U103") (pin "4") (pinfunction "2A_4") (pintype "input"))
      (node (ref "U103") (pin "9") (pinfunction "3A_9") (pintype "input"))
    )
    (net (code "56") (name "SD_DET") (class "Default")
      (node (ref "J102") (pin "10") (pinfunction "DSW2_10") (pintype "bidirectional"))
      (node (ref "R108") (pin "2") (pinfunction "2_2") (pintype "passive"))
      (node (ref "U101") (pin "31") (pinfunction "GPIO20_31") (pintype "bidirectional"))
    )
    (net (code "57") (name "SPI0_CS_BT") (class "Default")
      (node (ref "U101") (pin "7") (pinfunction "GPIO5_7") (pintype "bidirectional"))
    )
    (net (code "58") (name "SPI0_CS_GPS") (class "Default")
      (node (ref "U101") (pin "3") (pinfunction "GPIO1_3") (pintype "bidirectional"))
      (node (ref "U202") (pin "A2") (pinfunction "SDA_/_SPI_CS_N_A2") (pintype "passive"))
    )
    (net (code "59") (name "SPI0_CS_SD") (class "Default")
      (node (ref "J102") (pin "2") (pinfunction "CD/DAT3_2") (pintype "passive"))
      (node (ref "U101") (pin "28") (pinfunction "GPIO17_28") (pintype "bidirectional"))
    )
    (net (code "60") (name "SPI0_MISO") (class "Default")
      (node (ref "J102") (pin "7") (pinfunction "DAT0_7") (pintype "bidirectional"))
      (node (ref "U101") (pin "27") (pinfunction "GPIO16_27") (pintype "bidirectional"))
      (node (ref "U202") (pin "J5") (pinfunction "TXD/SPI_MISO_J5") (pintype "passive"))
    )
    (net (code "61") (name "SPI0_MOSI") (class "Default")
      (node (ref "J102") (pin "3") (pinfunction "CMD_3") (pintype "passive"))
      (node (ref "U101") (pin "30") (pinfunction "GPIO19_30") (pintype "bidirectional"))
      (node (ref "U202") (pin "J4") (pinfunction "RXD/SPI_MOSI_J4") (pintype "passive"))
    )
    (net (code "62") (name "SPI0_SCK") (class "Default")
      (node (ref "J102") (pin "5") (pinfunction "CLK_5") (pintype "passive"))
      (node (ref "U101") (pin "29") (pinfunction "GPIO18_29") (pintype "bidirectional"))
      (node (ref "U202") (pin "B1") (pinfunction "SCL_/_SPI_CLK_B1") (pintype "passive"))
    )
    (net (code "63") (name "SPI1_CS_SX") (class "Default")
      (node (ref "U101") (pin "16") (pinfunction "GPIO13_16") (pintype "bidirectional"))
      (node (ref "U201") (pin "19") (pinfunction "NSS_CTS_19") (pintype "input"))
    )
    (net (code "64") (name "SPI1_MISO") (class "Default")
      (node (ref "U101") (pin "15") (pinfunction "GPIO12_15") (pintype "bidirectional"))
      (node (ref "U201") (pin "16") (pinfunction "MISO_TX_16") (pintype "output"))
    )
    (net (code "65") (name "SPI1_MOSI") (class "Default")
      (node (ref "U101") (pin "14") (pinfunction "GPIO11_14") (pintype "bidirectional"))
      (node (ref "U201") (pin "17") (pinfunction "MOSI_RX_17") (pintype "input"))
    )
    (net (code "66") (name "SPI1_SCK") (class "Default")
      (node (ref "U101") (pin "13") (pinfunction "GPIO10_13") (pintype "bidirectional"))
      (node (ref "U201") (pin "18") (pinfunction "SCK_RTSN_18") (pintype "input"))
    )
    (net (code "67") (name "SWCLK") (class "Default")
      (node (ref "U101") (pin "24") (pinfunction "SWCLK_24") (pintype "passive"))
    )
    (net (code "68") (name "SWDIO") (class "Default")
      (node (ref "U101") (pin "25") (pinfunction "SWDIO_25") (pintype "passive"))
    )
    (net (code "69") (name "SX_BUSY") (class "Default")
      (node (ref "U101") (pin "34") (pinfunction "GPIO22_34") (pintype "bidirectional"))
      (node (ref "U201") (pin "7") (pinfunction "BUSY_7") (pintype "output"))
    )
    (net (code "70") (name "SX_NRESET") (class "Default")
      (node (ref "U103") (pin "3") (pinfunction "1Y_3") (pintype "output"))
      (node (ref "U201") (pin "3") (pinfunction "NRESET_3") (pintype "input"))
    )
    (net (code "71") (name "SX_NRESET_IO") (class "Default")
      (node (ref "U101") (pin "32") (pinfunction "GPIO21_32") (pintype "bidirectional"))
      (node (ref "U103") (pin "2") (pinfunction "1B_2") (pintype "input"))
    )
    (net (code "72") (name "USB_D+") (class "Default")
      (node (ref "J101") (pin "A6") (pinfunction "DP1_A6") (pintype "bidirectional"))
      (node (ref "J101") (pin "B6") (pinfunction "DP2_B6") (pintype "bidirectional"))
      (node (ref "R102") (pin "2") (pinfunction "2_2") (pintype "passive"))
    )
    (net (code "73") (name "USB_D-") (class "Default")
      (node (ref "J101") (pin "A7") (pinfunction "DN1_A7") (pintype "bidirectional"))
      (node (ref "J101") (pin "B7") (pinfunction "DN2_B7") (pintype "bidirectional"))
      (node (ref "R103") (pin "2") (pinfunction "2_2") (pintype "passive"))
    )
    (net (code "74") (name "XIN") (class "Default")
      (node (ref "C112") (pin "1") (pinfunction "1_1") (pintype "passive"))
      (node (ref "U101") (pin "20") (pinfunction "XIN_20") (pintype "passive"))
      (node (ref "X101") (pin "2") (pinfunction "2_2") (pintype "passive"))
    )
    (net (code "75") (name "XOUT") (class "Default")
      (node (ref "R101") (pin "2") (pinfunction "2_2") (pintype "passive"))
      (node (ref "U101") (pin "21") (pinfunction "XOUT_21") (pintype "output"))
    )
    (net (code "76") (name "unconnected-(J101-SBU1-PadA8)") (class "Default")
      (node (ref "J101") (pin "A8") (pinfunction "SBU1_A8") (pintype "bidirectional"))
    )
    (net (code "77") (name "unconnected-(J101-SBU2-PadB8)") (class "Default")
      (node (ref "J101") (pin "B8") (pinfunction "SBU2_B8") (pintype "bidirectional"))
    )
    (net (code "78") (name "unconnected-(J102-DAT1-Pad8)") (class "Default")
      (node (ref "J102") (pin "8") (pinfunction "DAT1_8") (pintype "bidirectional"))
    )
    (net (code "79") (name "unconnected-(J102-DAT2-Pad1)") (class "Default")
      (node (ref "J102") (pin "1") (pinfunction "DAT2_1") (pintype "bidirectional"))
    )
    (net (code "80") (name "unconnected-(U103-4B-Pad13)") (class "Default")
      (node (ref "U103") (pin "13") (pinfunction "4B_13") (pintype "input"))
    )
    (net (code "81") (name "unconnected-(U103-4Y-Pad11)") (class "Default")
      (node (ref "U103") (pin "11") (pinfunction "4Y_11") (pintype "output"))
    )
    (net (code "82") (name "unconnected-(U201-DIO1-Pad8)") (class "Default")
      (node (ref "U201") (pin "8") (pinfunction "DIO1_8") (pintype "bidirectional"))
    )
    (net (code "83") (name "unconnected-(U201-DIO2-Pad9)") (class "Default")
      (node (ref "U201") (pin "9") (pinfunction "DIO2_9") (pintype "bidirectional"))
    )
    (net (code "84") (name "unconnected-(U201-DIO3-Pad10)") (class "Default")
      (node (ref "U201") (pin "10") (pinfunction "DIO3_10") (pintype "bidirectional"))
    )
    (net (code "85") (name "unconnected-(U202-PIO14-PadF6)") (class "Default")
      (node (ref "U202") (pin "F6") (pinfunction "PIO14_F6") (pintype "bidirectional"))
    )
    (net (code "86") (name "unconnected-(U202-PIO15-PadC6)") (class "Default")
      (node (ref "U202") (pin "C6") (pinfunction "PIO15_C6") (pintype "bidirectional"))
    )
    (net (code "87") (name "unconnected-(U202-RESERVED-PadG9)") (class "Default")
      (node (ref "U202") (pin "G9") (pinfunction "RESERVED_G9") (pintype "passive"))
    )
    (net (code "88") (name "unconnected-(U202-RESERVED_2-PadA6)") (class "Default")
      (node (ref "U202") (pin "A6") (pinfunction "RESERVED_2_A6") (pintype "passive"))
    )
    (net (code "89") (name "unconnected-(U202-RESERVED_3-PadE9)") (class "Default")
      (node (ref "U202") (pin "E9") (pinfunction "RESERVED_3_E9") (pintype "passive"))
    )
    (net (code "90") (name "unconnected-(U202-RESERVED_4-PadF1)") (class "Default")
      (node (ref "U202") (pin "F1") (pinfunction "RESERVED_4_F1") (pintype "passive"))
    )
    (net (code "91") (name "unconnected-(U202-RESERVED_5-PadF4)") (class "Default")
      (node (ref "U202") (pin "F4") (pinfunction "RESERVED_5_F4") (pintype "passive"))
    )
    (net (code "92") (name "unconnected-(U202-RESERVED_6-PadF9)") (class "Default")
      (node (ref "U202") (pin "F9") (pinfunction "RESERVED_6_F9") (pintype "passive"))
    )
    (net (code "93") (name "unconnected-(U202-RESERVED_7-PadG5)") (class "Default")
      (node (ref "U202") (pin "G5") (pinfunction "RESERVED_7_G5") (pintype "passive"))
    )
    (net (code "94") (name "unconnected-(U202-SAFEBOOT_N-PadC4)") (class "Default")
      (node (ref "U202") (pin "C4") (pinfunction "SAFEBOOT_N_C4") (pintype "passive"))
    )
    (net (code "95") (name "unconnected-(U202-SQI_CLK-PadE1)") (class "Default")
      (node (ref "U202") (pin "E1") (pinfunction "SQI_CLK_E1") (pintype "passive"))
    )
    (net (code "96") (name "unconnected-(U202-SQI_CS_N-PadD3)") (class "Default")
      (node (ref "U202") (pin "D3") (pinfunction "SQI_CS_N_D3") (pintype "passive"))
    )
    (net (code "97") (name "unconnected-(U202-SQI_D0-PadD1)") (class "Default")
      (node (ref "U202") (pin "D1") (pinfunction "SQI_D0_D1") (pintype "bidirectional"))
    )
    (net (code "98") (name "unconnected-(U202-SQI_D1-PadC1)") (class "Default")
      (node (ref "U202") (pin "C1") (pinfunction "SQI_D1_C1") (pintype "bidirectional"))
    )
    (net (code "99") (name "unconnected-(U202-SQI_D2-PadE3)") (class "Default")
      (node (ref "U202") (pin "E3") (pinfunction "SQI_D2_E3") (pintype "bidirectional"))
    )
    (net (code "100") (name "unconnected-(U202-SQI_D3-PadF3)") (class "Default")
      (node (ref "U202") (pin "F3") (pinfunction "SQI_D3_F3") (pintype "bidirectional"))
    )
    (net (code "101") (name "unconnected-(U202-TIMEPULSE-PadC3)") (class "Default")
      (node (ref "U202") (pin "C3") (pinfunction "TIMEPULSE_C3") (pintype "passive"))
    )
  )
)
